# HYDRA_V3_NAV_CRIPPLED.net
KiCad netlist of a schematic drawn in Altium Designer
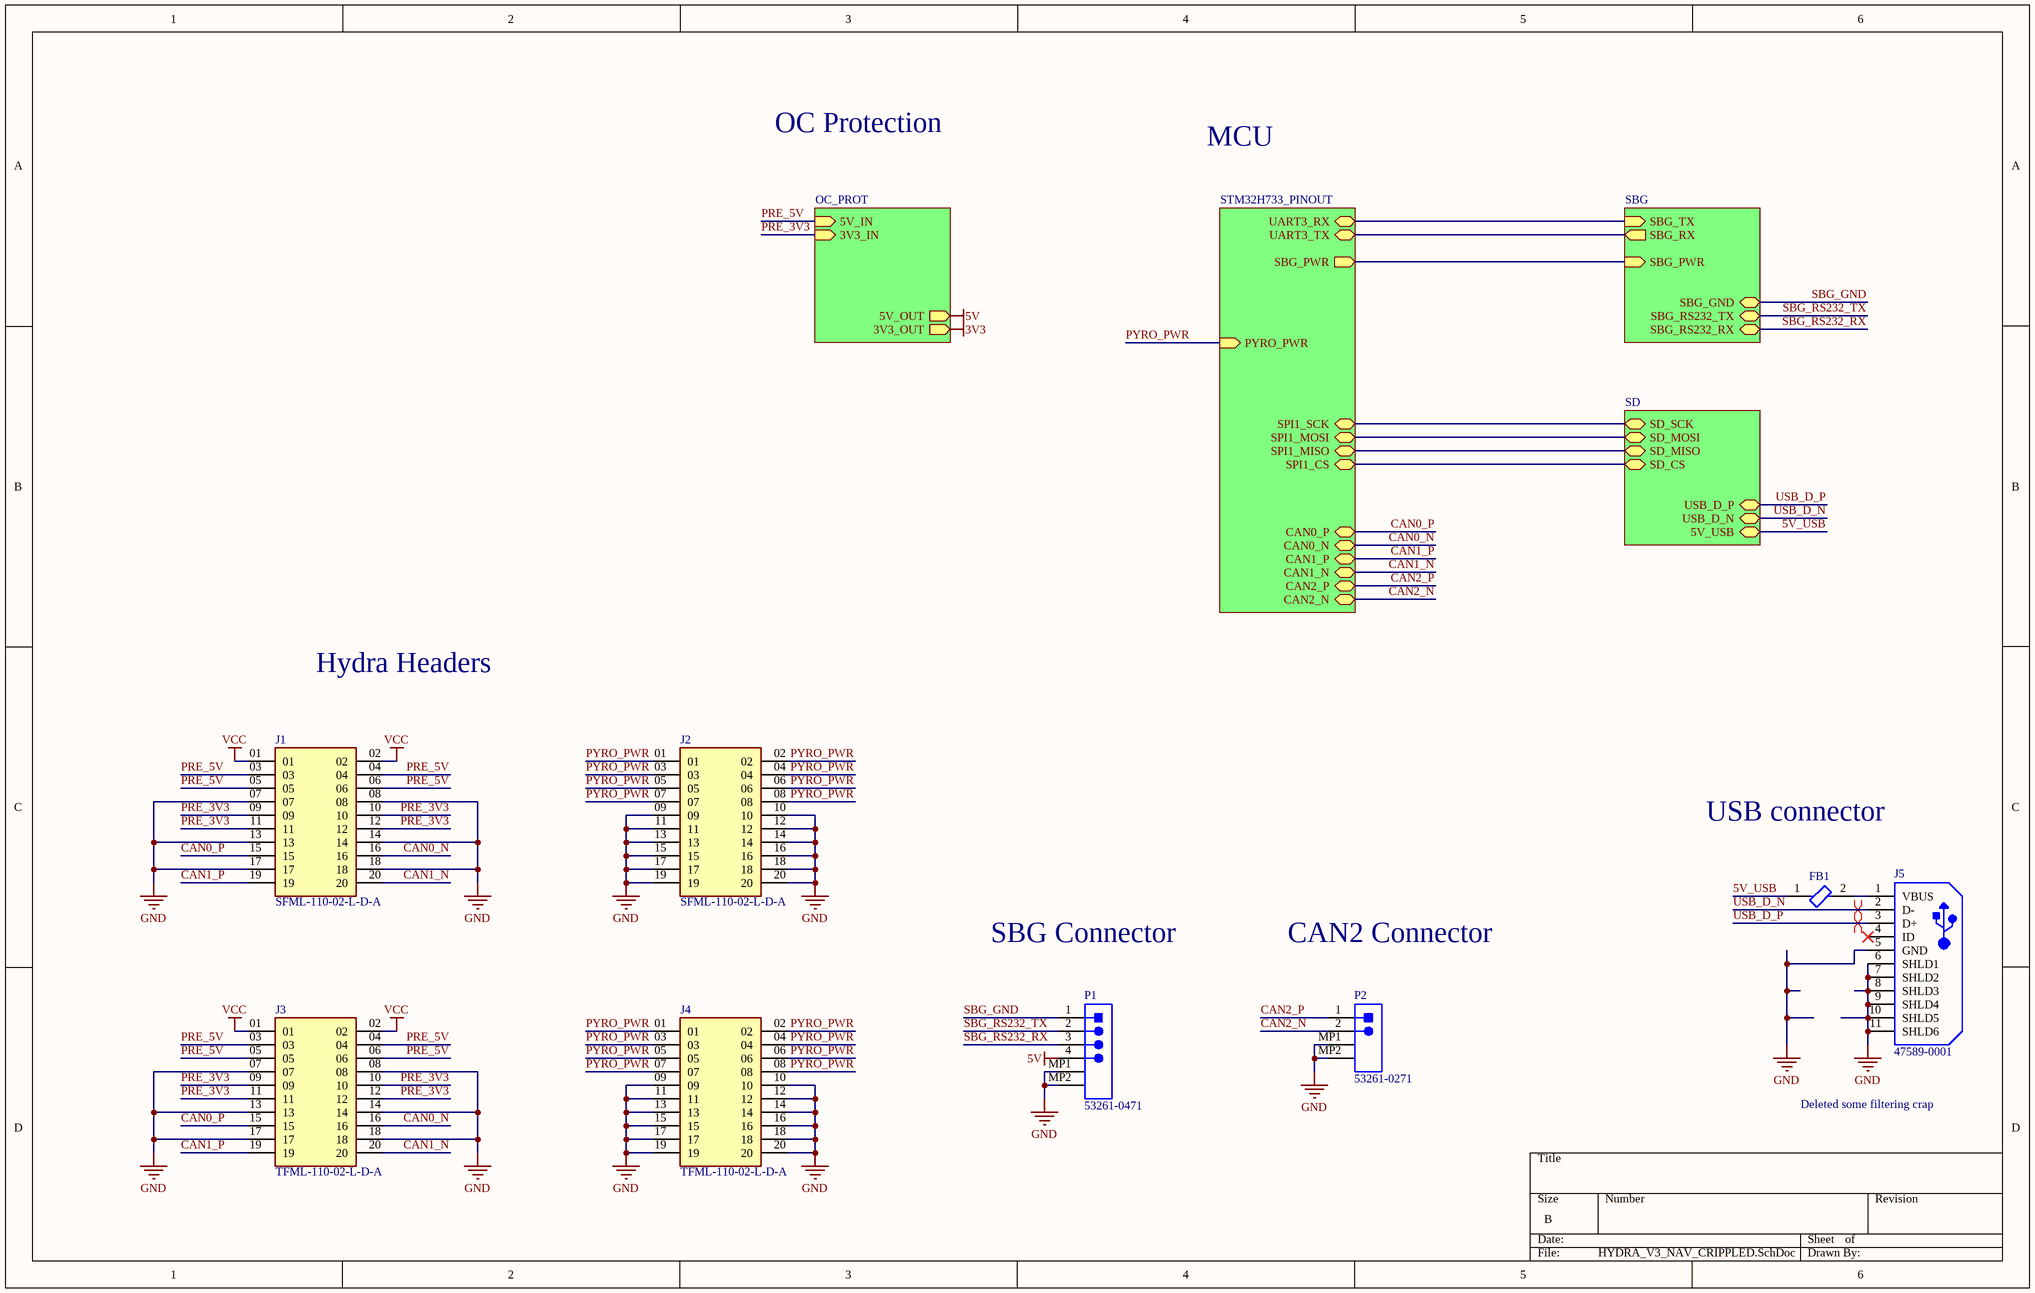
[diagram p0: HYDRA_V3_NAV_CRIPPLED.SchDoc]

(export (version "E")
  (design (tool "Eeschema 10.0.6"))
  (components
    (comp (ref "FB1")
      (value "BLM18PG121SN1D")
      (footprint "FP-BLM18-0_15-t0_8-IPC_A")
      (description "Chip Ferrite Bead, 0603, 120Ω @ 100MHz, 0.05Ω, 25%, 2A")
      (fields (field (name "TOLERANCE") "25%"))
      (libsource (lib "Altium Content Vault") (part "5f30dd21d616792df468990f7003faa"))
    )
    (comp (ref "J1")
      (value "SFML-110-02-L-D-A")
      (footprint "SFML-110-02-L-D-A-Footprint-1")
      (description "Headers & Wire Housings .050 Tiger Eye High-Reliability Locking Socket Strip")
      (libsource (lib "uORocketry Hardware") (part "SFML-110-02-L-D-A"))
    )
    (comp (ref "J2")
      (value "SFML-110-02-L-D-A")
      (footprint "SFML-110-02-L-D-A-Footprint-1")
      (description "Headers & Wire Housings .050 Tiger Eye High-Reliability Locking Socket Strip")
      (libsource (lib "uORocketry Hardware") (part "SFML-110-02-L-D-A"))
    )
    (comp (ref "J3")
      (value "TFML-110-02-L-D-A")
      (footprint "TFML-110-02-L-D-A-Footprint-1")
      (description "Conn Shrouded Header (4 Sides) HDR 20 POS 1.27mm Solder ST Top Entry SMD TIGER EYE™ Tube")
      (libsource (lib "uORocketry Hardware") (part "TFML-110-02-L-D-A"))
    )
    (comp (ref "J4")
      (value "TFML-110-02-L-D-A")
      (footprint "TFML-110-02-L-D-A-Footprint-1")
      (description "Conn Shrouded Header (4 Sides) HDR 20 POS 1.27mm Solder ST Top Entry SMD TIGER EYE™ Tube")
      (libsource (lib "uORocketry Hardware") (part "TFML-110-02-L-D-A"))
    )
    (comp (ref "J5")
      (value "47589-0001")
      (footprint "MOLX-47589-0001_V")
      (description "Right Angle Female Type AB Micro USB Connector, 30 V, 1.8 A, -30 to 85 degC, RoHS, Tape and Reel")
      (fields (field (name "MANUFACTURER") "Molex"))
      (libsource (lib "Altium Content Vault") (part "USB-5-6SHLD"))
    )
    (comp (ref "P1")
      (value "53261-0471")
      (footprint "MOLEX-53261-0471_V")
      (description "Male Header, Pitch 1.25 mm, 1 x 4 Position, Height 3.4 mm, -40 to 85 degC, RoHS, Tape and Reel")
      (fields (field (name "MANUFACTURER") "Molex"))
      (libsource (lib "Altium Content Vault") (part "CN-1P-2M-R4_A"))
    )
    (comp (ref "P2")
      (value "53261-0271")
      (footprint "MOLX-53261-0271_V")
      (description "PicoBlade(TM) Header, Right Angle, -40 to 85 degC, 2-Pin SMD, RoHS, Tape and Reel")
      (fields (field (name "MANUFACTURER") "Molex"))
      (libsource (lib "Altium Content Vault") (part "CN-1P-2M-R2"))
    )
  )
  (nets
    (net (code "1") (name "/5V_USB") (class "Default")
      (node (ref "FB1") (pin "1") (pinfunction "1_1") (pintype "passive"))
    )
    (net (code "2") (name "/CAN0_N") (class "Default")
      (node (ref "J1") (pin "16") (pinfunction "16_16") (pintype "passive"))
      (node (ref "J3") (pin "16") (pinfunction "16_16") (pintype "passive"))
    )
    (net (code "3") (name "/CAN0_P") (class "Default")
      (node (ref "J1") (pin "15") (pinfunction "15_15") (pintype "passive"))
      (node (ref "J3") (pin "15") (pinfunction "15_15") (pintype "passive"))
    )
    (net (code "4") (name "/CAN1_N") (class "Default")
      (node (ref "J1") (pin "20") (pinfunction "20_20") (pintype "passive"))
      (node (ref "J3") (pin "20") (pinfunction "20_20") (pintype "passive"))
    )
    (net (code "5") (name "/CAN1_P") (class "Default")
      (node (ref "J1") (pin "19") (pinfunction "19_19") (pintype "passive"))
      (node (ref "J3") (pin "19") (pinfunction "19_19") (pintype "passive"))
    )
    (net (code "6") (name "/CAN2_N") (class "Default")
      (node (ref "P2") (pin "2") (pinfunction "2_2") (pintype "passive"))
    )
    (net (code "7") (name "/CAN2_P") (class "Default")
      (node (ref "P2") (pin "1") (pinfunction "1_1") (pintype "passive"))
    )
    (net (code "8") (name "/PRE_3V3") (class "Default")
      (node (ref "J1") (pin "09") (pinfunction "09_09") (pintype "passive"))
      (node (ref "J1") (pin "10") (pinfunction "10_10") (pintype "passive"))
      (node (ref "J1") (pin "11") (pinfunction "11_11") (pintype "passive"))
      (node (ref "J1") (pin "12") (pinfunction "12_12") (pintype "passive"))
      (node (ref "J3") (pin "09") (pinfunction "09_09") (pintype "passive"))
      (node (ref "J3") (pin "10") (pinfunction "10_10") (pintype "passive"))
      (node (ref "J3") (pin "11") (pinfunction "11_11") (pintype "passive"))
      (node (ref "J3") (pin "12") (pinfunction "12_12") (pintype "passive"))
    )
    (net (code "9") (name "/PRE_5V") (class "Default")
      (node (ref "J1") (pin "03") (pinfunction "03_03") (pintype "passive"))
      (node (ref "J1") (pin "04") (pinfunction "04_04") (pintype "passive"))
      (node (ref "J1") (pin "05") (pinfunction "05_05") (pintype "passive"))
      (node (ref "J1") (pin "06") (pinfunction "06_06") (pintype "passive"))
      (node (ref "J3") (pin "03") (pinfunction "03_03") (pintype "passive"))
      (node (ref "J3") (pin "04") (pinfunction "04_04") (pintype "passive"))
      (node (ref "J3") (pin "05") (pinfunction "05_05") (pintype "passive"))
      (node (ref "J3") (pin "06") (pinfunction "06_06") (pintype "passive"))
    )
    (net (code "10") (name "/PYRO_PWR") (class "Default")
      (node (ref "J2") (pin "01") (pinfunction "01_01") (pintype "passive"))
      (node (ref "J2") (pin "02") (pinfunction "02_02") (pintype "passive"))
      (node (ref "J2") (pin "03") (pinfunction "03_03") (pintype "passive"))
      (node (ref "J2") (pin "04") (pinfunction "04_04") (pintype "passive"))
      (node (ref "J2") (pin "05") (pinfunction "05_05") (pintype "passive"))
      (node (ref "J2") (pin "06") (pinfunction "06_06") (pintype "passive"))
      (node (ref "J2") (pin "07") (pinfunction "07_07") (pintype "passive"))
      (node (ref "J2") (pin "08") (pinfunction "08_08") (pintype "passive"))
      (node (ref "J4") (pin "01") (pinfunction "01_01") (pintype "passive"))
      (node (ref "J4") (pin "02") (pinfunction "02_02") (pintype "passive"))
      (node (ref "J4") (pin "03") (pinfunction "03_03") (pintype "passive"))
      (node (ref "J4") (pin "04") (pinfunction "04_04") (pintype "passive"))
      (node (ref "J4") (pin "05") (pinfunction "05_05") (pintype "passive"))
      (node (ref "J4") (pin "06") (pinfunction "06_06") (pintype "passive"))
      (node (ref "J4") (pin "07") (pinfunction "07_07") (pintype "passive"))
      (node (ref "J4") (pin "08") (pinfunction "08_08") (pintype "passive"))
    )
    (net (code "11") (name "/SBG_GND") (class "Default")
      (node (ref "P1") (pin "1") (pinfunction "1_1") (pintype "passive"))
    )
    (net (code "13") (name "/SBG_RS232_RX") (class "Default")
      (node (ref "P1") (pin "3") (pinfunction "3_3") (pintype "passive"))
    )
    (net (code "14") (name "/SBG_RS232_TX") (class "Default")
      (node (ref "P1") (pin "2") (pinfunction "2_2") (pintype "passive"))
    )
    (net (code "21") (name "/USB_D_N") (class "Default")
      (node (ref "J5") (pin "2") (pinfunction "D-_2") (pintype "passive"))
    )
    (net (code "22") (name "/USB_D_P") (class "Default")
      (node (ref "J5") (pin "3") (pinfunction "D+_3") (pintype "passive"))
    )
    (net (code "24") (name "5V") (class "Default")
      (node (ref "P1") (pin "4") (pinfunction "4_4") (pintype "passive"))
    )
    (net (code "25") (name "GND") (class "Default")
      (node (ref "J1") (pin "07") (pinfunction "07_07") (pintype "passive"))
      (node (ref "J1") (pin "08") (pinfunction "08_08") (pintype "passive"))
      (node (ref "J1") (pin "13") (pinfunction "13_13") (pintype "passive"))
      (node (ref "J1") (pin "14") (pinfunction "14_14") (pintype "passive"))
      (node (ref "J1") (pin "17") (pinfunction "17_17") (pintype "passive"))
      (node (ref "J1") (pin "18") (pinfunction "18_18") (pintype "passive"))
      (node (ref "J2") (pin "09") (pinfunction "09_09") (pintype "passive"))
      (node (ref "J2") (pin "10") (pinfunction "10_10") (pintype "passive"))
      (node (ref "J2") (pin "11") (pinfunction "11_11") (pintype "passive"))
      (node (ref "J2") (pin "12") (pinfunction "12_12") (pintype "passive"))
      (node (ref "J2") (pin "13") (pinfunction "13_13") (pintype "passive"))
      (node (ref "J2") (pin "14") (pinfunction "14_14") (pintype "passive"))
      (node (ref "J2") (pin "15") (pinfunction "15_15") (pintype "passive"))
      (node (ref "J2") (pin "16") (pinfunction "16_16") (pintype "passive"))
      (node (ref "J2") (pin "17") (pinfunction "17_17") (pintype "passive"))
      (node (ref "J2") (pin "18") (pinfunction "18_18") (pintype "passive"))
      (node (ref "J2") (pin "19") (pinfunction "19_19") (pintype "passive"))
      (node (ref "J2") (pin "20") (pinfunction "20_20") (pintype "passive"))
      (node (ref "J3") (pin "07") (pinfunction "07_07") (pintype "passive"))
      (node (ref "J3") (pin "08") (pinfunction "08_08") (pintype "passive"))
      (node (ref "J3") (pin "13") (pinfunction "13_13") (pintype "passive"))
      (node (ref "J3") (pin "14") (pinfunction "14_14") (pintype "passive"))
      (node (ref "J3") (pin "17") (pinfunction "17_17") (pintype "passive"))
      (node (ref "J3") (pin "18") (pinfunction "18_18") (pintype "passive"))
      (node (ref "J4") (pin "09") (pinfunction "09_09") (pintype "passive"))
      (node (ref "J4") (pin "10") (pinfunction "10_10") (pintype "passive"))
      (node (ref "J4") (pin "11") (pinfunction "11_11") (pintype "passive"))
      (node (ref "J4") (pin "12") (pinfunction "12_12") (pintype "passive"))
      (node (ref "J4") (pin "13") (pinfunction "13_13") (pintype "passive"))
      (node (ref "J4") (pin "14") (pinfunction "14_14") (pintype "passive"))
      (node (ref "J4") (pin "15") (pinfunction "15_15") (pintype "passive"))
      (node (ref "J4") (pin "16") (pinfunction "16_16") (pintype "passive"))
      (node (ref "J4") (pin "17") (pinfunction "17_17") (pintype "passive"))
      (node (ref "J4") (pin "18") (pinfunction "18_18") (pintype "passive"))
      (node (ref "J4") (pin "19") (pinfunction "19_19") (pintype "passive"))
      (node (ref "J4") (pin "20") (pinfunction "20_20") (pintype "passive"))
      (node (ref "J5") (pin "10") (pinfunction "SHLD5_10") (pintype "passive"))
      (node (ref "J5") (pin "11") (pinfunction "SHLD6_11") (pintype "passive"))
      (node (ref "J5") (pin "5") (pinfunction "GND_5") (pintype "passive"))
      (node (ref "J5") (pin "6") (pinfunction "SHLD1_6") (pintype "passive"))
      (node (ref "J5") (pin "7") (pinfunction "SHLD2_7") (pintype "passive"))
      (node (ref "J5") (pin "8") (pinfunction "SHLD3_8") (pintype "passive"))
      (node (ref "J5") (pin "9") (pinfunction "SHLD4_9") (pintype "passive"))
      (node (ref "P1") (pin "MP1") (pinfunction "MP1_MP1") (pintype "passive"))
      (node (ref "P1") (pin "MP2") (pinfunction "MP2_MP2") (pintype "passive"))
      (node (ref "P2") (pin "MP1") (pinfunction "MP1_MP1") (pintype "passive"))
      (node (ref "P2") (pin "MP2") (pinfunction "MP2_MP2") (pintype "passive"))
    )
    (net (code "26") (name "Net-(J5-VBUS)") (class "Default")
      (node (ref "FB1") (pin "2") (pinfunction "2_2") (pintype "passive"))
      (node (ref "J5") (pin "1") (pinfunction "VBUS_1") (pintype "passive"))
    )
    (net (code "27") (name "VCC") (class "Default")
      (node (ref "J1") (pin "01") (pinfunction "01_01") (pintype "passive"))
      (node (ref "J1") (pin "02") (pinfunction "02_02") (pintype "passive"))
      (node (ref "J3") (pin "01") (pinfunction "01_01") (pintype "passive"))
      (node (ref "J3") (pin "02") (pinfunction "02_02") (pintype "passive"))
    )
    (net (code "28") (name "unconnected-(J5-ID-Pad4)") (class "Default")
      (node (ref "J5") (pin "4") (pinfunction "ID_4") (pintype "passive+no_connect"))
    )
  )
)
